# Femtoduino.net
KiCad netlist of a schematic drawn in EAGLE
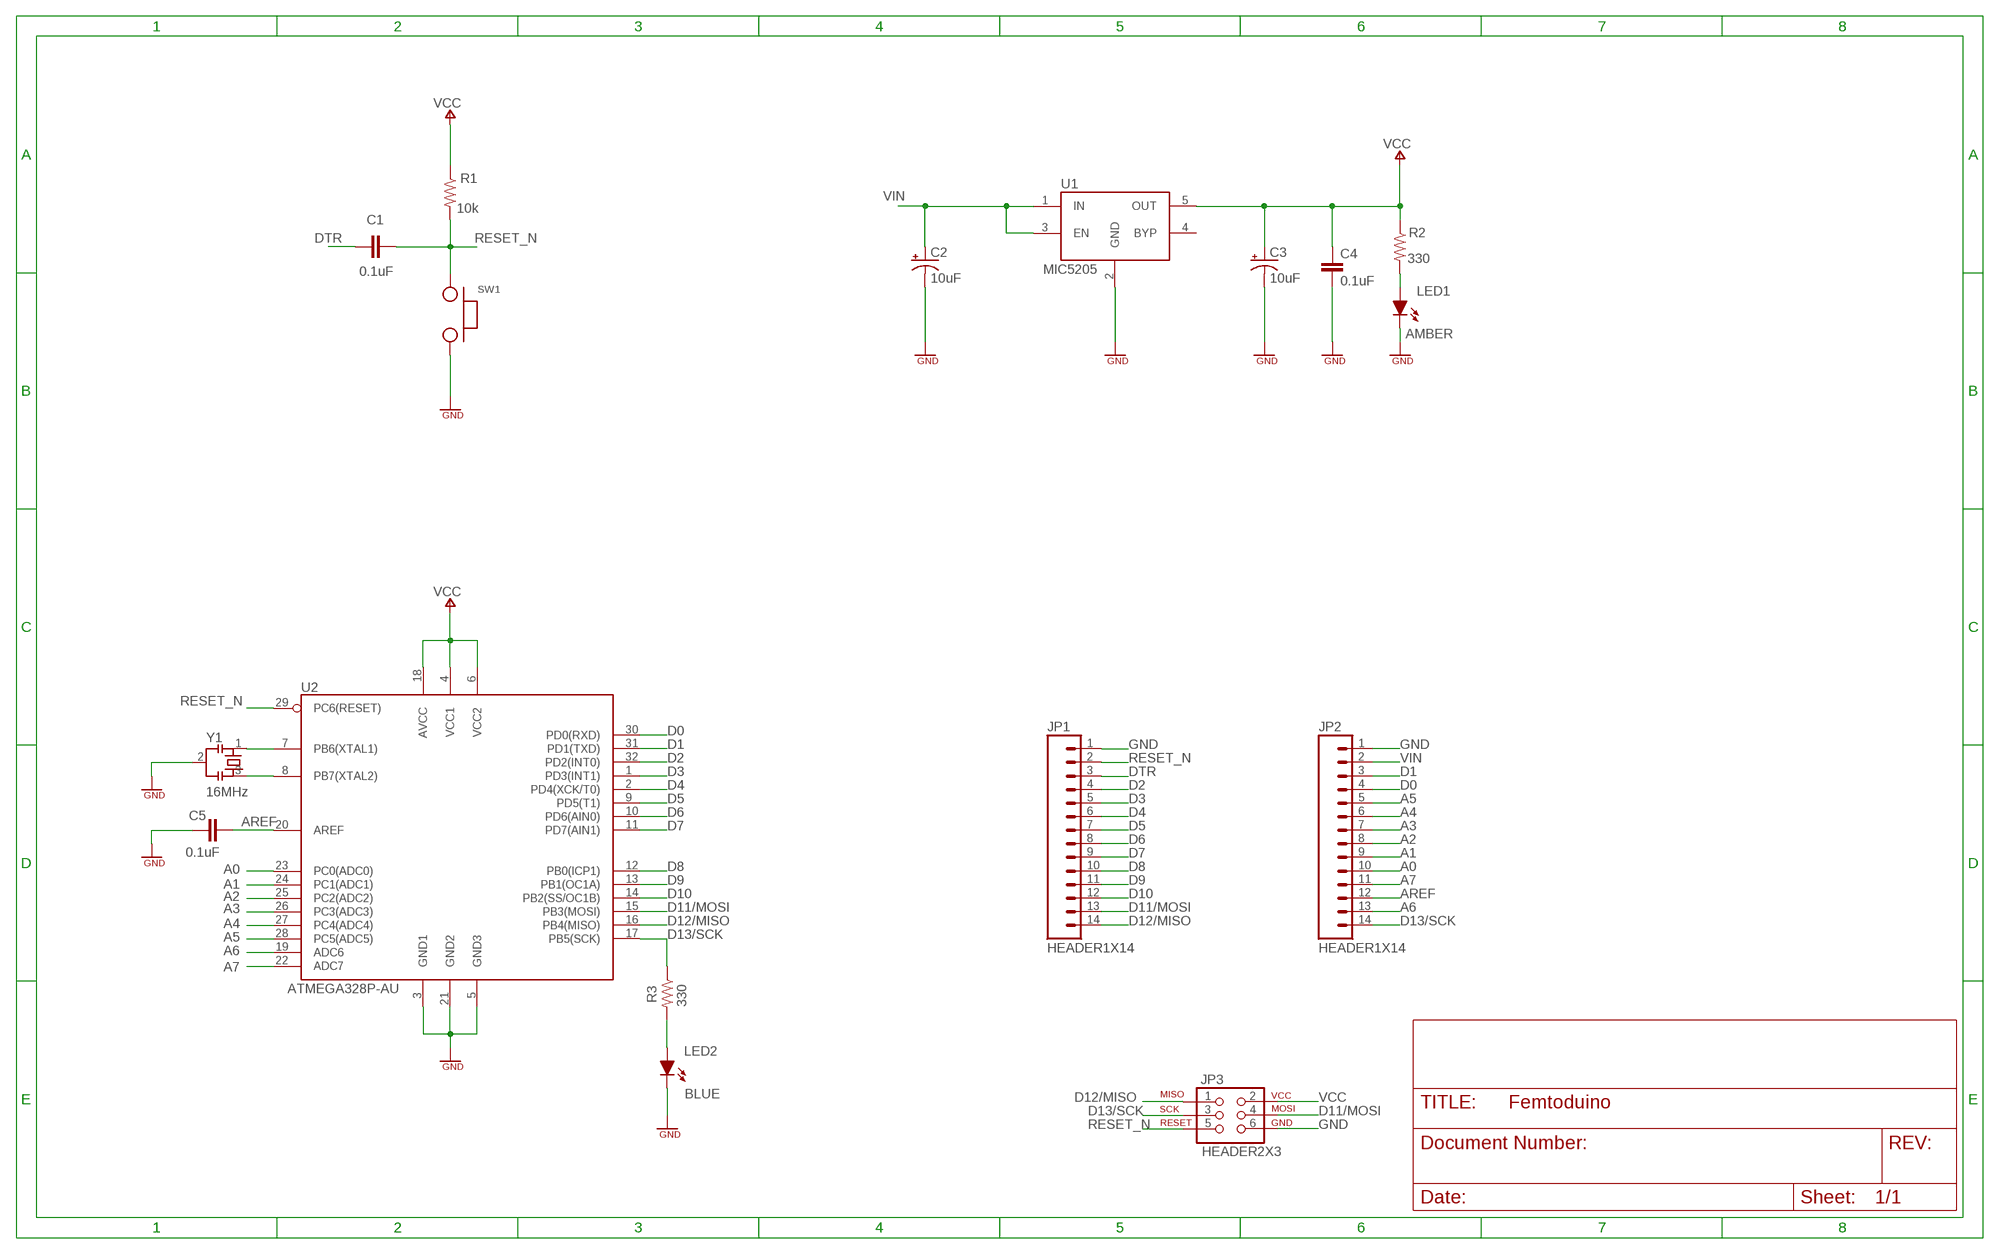
[diagram p0: schematic, sheet 1]

(export (version "E")
  (design (tool "Eeschema 10.0.6"))
  (components
    (comp (ref "C1")
      (value "0.1uF")
      (footprint "eagle-import:SMD0603")
      (libsource (lib "eagle-import") (part "CAP_0603"))
    )
    (comp (ref "C2")
      (value "10uF")
      (footprint "eagle-import:EIA3216")
      (libsource (lib "eagle-import") (part "CAP_TANT"))
    )
    (comp (ref "C3")
      (value "10uF")
      (footprint "eagle-import:EIA3216")
      (libsource (lib "eagle-import") (part "CAP_TANT"))
    )
    (comp (ref "C4")
      (value "0.1uF")
      (footprint "eagle-import:SMD0603")
      (libsource (lib "eagle-import") (part "CAP_0603"))
    )
    (comp (ref "C5")
      (value "0.1uF")
      (footprint "eagle-import:SMD0603")
      (libsource (lib "eagle-import") (part "CAP_0603"))
    )
    (comp (ref "JP1")
      (value "HEADER1X14")
      (footprint "eagle-import:1X14")
      (libsource (lib "eagle-import") (part "HEADER1X14"))
    )
    (comp (ref "JP2")
      (value "HEADER1X14")
      (footprint "eagle-import:1X14")
      (libsource (lib "eagle-import") (part "HEADER1X14"))
    )
    (comp (ref "JP3")
      (value "HEADER2X3")
      (footprint "eagle-import:2X3")
      (libsource (lib "eagle-import") (part "HEADER2X3"))
    )
    (comp (ref "LED1")
      (value "AMBER")
      (footprint "eagle-import:LED_0805")
      (libsource (lib "eagle-import") (part "LED_0805"))
    )
    (comp (ref "LED2")
      (value "BLUE")
      (footprint "eagle-import:LED_0805")
      (libsource (lib "eagle-import") (part "LED_0805"))
    )
    (comp (ref "R1")
      (value "10k")
      (footprint "eagle-import:SMD0603")
      (libsource (lib "eagle-import") (part "RES_0603"))
    )
    (comp (ref "R2")
      (value "330")
      (footprint "eagle-import:SMD0603")
      (libsource (lib "eagle-import") (part "RES_0603"))
    )
    (comp (ref "R3")
      (value "330")
      (footprint "eagle-import:SMD0603")
      (libsource (lib "eagle-import") (part "RES_0603"))
    )
    (comp (ref "SW1")
      (value "SWITCH")
      (footprint "eagle-import:SWITCH-SPST")
      (libsource (lib "eagle-import") (part "SWITCH"))
    )
    (comp (ref "U1")
      (value "MIC5205")
      (footprint "eagle-import:SOT23-5")
      (libsource (lib "eagle-import") (part "MIC5205"))
    )
    (comp (ref "U2")
      (value "ATMEGA328P-AU")
      (footprint "eagle-import:TQFP32")
      (libsource (lib "eagle-import") (part "ATMEGA328P-AU"))
    )
    (comp (ref "Y1")
      (value "16MHz")
      (footprint "eagle-import:CSTCE")
      (libsource (lib "eagle-import") (part "CSTCE"))
    )
  )
  (nets
    (net (code "1") (name "/A0") (class "Default")
      (node (ref "JP2") (pin "10") (pinfunction "10_10") (pintype "passive"))
      (node (ref "U2") (pin "23") (pinfunction "PC0(ADC0)_23") (pintype "bidirectional"))
    )
    (net (code "2") (name "/A1") (class "Default")
      (node (ref "JP2") (pin "9") (pinfunction "9_9") (pintype "passive"))
      (node (ref "U2") (pin "24") (pinfunction "PC1(ADC1)_24") (pintype "bidirectional"))
    )
    (net (code "3") (name "/A2") (class "Default")
      (node (ref "JP2") (pin "8") (pinfunction "8_8") (pintype "passive"))
      (node (ref "U2") (pin "25") (pinfunction "PC2(ADC2)_25") (pintype "bidirectional"))
    )
    (net (code "4") (name "/A3") (class "Default")
      (node (ref "JP2") (pin "7") (pinfunction "7_7") (pintype "passive"))
      (node (ref "U2") (pin "26") (pinfunction "PC3(ADC3)_26") (pintype "bidirectional"))
    )
    (net (code "5") (name "/A4") (class "Default")
      (node (ref "JP2") (pin "6") (pinfunction "6_6") (pintype "passive"))
      (node (ref "U2") (pin "27") (pinfunction "PC4(ADC4)_27") (pintype "bidirectional"))
    )
    (net (code "6") (name "/A5") (class "Default")
      (node (ref "JP2") (pin "5") (pinfunction "5_5") (pintype "passive"))
      (node (ref "U2") (pin "28") (pinfunction "PC5(ADC5)_28") (pintype "bidirectional"))
    )
    (net (code "7") (name "/A6") (class "Default")
      (node (ref "JP2") (pin "13") (pinfunction "13_13") (pintype "passive"))
      (node (ref "U2") (pin "19") (pinfunction "ADC6_19") (pintype "bidirectional"))
    )
    (net (code "8") (name "/A7") (class "Default")
      (node (ref "JP2") (pin "11") (pinfunction "11_11") (pintype "passive"))
      (node (ref "U2") (pin "22") (pinfunction "ADC7_22") (pintype "bidirectional"))
    )
    (net (code "9") (name "/AREF") (class "Default")
      (node (ref "C5") (pin "2") (pinfunction "2_2") (pintype "passive"))
      (node (ref "JP2") (pin "12") (pinfunction "12_12") (pintype "passive"))
      (node (ref "U2") (pin "20") (pinfunction "AREF_20") (pintype "bidirectional"))
    )
    (net (code "10") (name "/D0") (class "Default")
      (node (ref "JP2") (pin "4") (pinfunction "4_4") (pintype "passive"))
      (node (ref "U2") (pin "30") (pinfunction "PD0(RXD)_30") (pintype "bidirectional"))
    )
    (net (code "11") (name "/D1") (class "Default")
      (node (ref "JP2") (pin "3") (pinfunction "3_3") (pintype "passive"))
      (node (ref "U2") (pin "31") (pinfunction "PD1(TXD)_31") (pintype "bidirectional"))
    )
    (net (code "12") (name "/D2") (class "Default")
      (node (ref "JP1") (pin "4") (pinfunction "4_4") (pintype "passive"))
      (node (ref "U2") (pin "32") (pinfunction "PD2(INT0)_32") (pintype "bidirectional"))
    )
    (net (code "13") (name "/D3") (class "Default")
      (node (ref "JP1") (pin "5") (pinfunction "5_5") (pintype "passive"))
      (node (ref "U2") (pin "1") (pinfunction "PD3(INT1)_1") (pintype "bidirectional"))
    )
    (net (code "14") (name "/D4") (class "Default")
      (node (ref "JP1") (pin "6") (pinfunction "6_6") (pintype "passive"))
      (node (ref "U2") (pin "2") (pinfunction "PD4(XCK/T0)_2") (pintype "bidirectional"))
    )
    (net (code "15") (name "/D5") (class "Default")
      (node (ref "JP1") (pin "7") (pinfunction "7_7") (pintype "passive"))
      (node (ref "U2") (pin "9") (pinfunction "PD5(T1)_9") (pintype "bidirectional"))
    )
    (net (code "16") (name "/D6") (class "Default")
      (node (ref "JP1") (pin "8") (pinfunction "8_8") (pintype "passive"))
      (node (ref "U2") (pin "10") (pinfunction "PD6(AIN0)_10") (pintype "bidirectional"))
    )
    (net (code "17") (name "/D7") (class "Default")
      (node (ref "JP1") (pin "9") (pinfunction "9_9") (pintype "passive"))
      (node (ref "U2") (pin "11") (pinfunction "PD7(AIN1)_11") (pintype "bidirectional"))
    )
    (net (code "18") (name "/D8") (class "Default")
      (node (ref "JP1") (pin "10") (pinfunction "10_10") (pintype "passive"))
      (node (ref "U2") (pin "12") (pinfunction "PB0(ICP1)_12") (pintype "bidirectional"))
    )
    (net (code "19") (name "/D9") (class "Default")
      (node (ref "JP1") (pin "11") (pinfunction "11_11") (pintype "passive"))
      (node (ref "U2") (pin "13") (pinfunction "PB1(OC1A)_13") (pintype "bidirectional"))
    )
    (net (code "20") (name "/D10") (class "Default")
      (node (ref "JP1") (pin "12") (pinfunction "12_12") (pintype "passive"))
      (node (ref "U2") (pin "14") (pinfunction "PB2(SS/OC1B)_14") (pintype "bidirectional"))
    )
    (net (code "21") (name "/D11{slash}MOSI") (class "Default")
      (node (ref "JP1") (pin "13") (pinfunction "13_13") (pintype "passive"))
      (node (ref "JP3") (pin "4") (pinfunction "4_4") (pintype "passive"))
      (node (ref "U2") (pin "15") (pinfunction "PB3(MOSI)_15") (pintype "bidirectional"))
    )
    (net (code "22") (name "/D12{slash}MISO") (class "Default")
      (node (ref "JP1") (pin "14") (pinfunction "14_14") (pintype "passive"))
      (node (ref "JP3") (pin "1") (pinfunction "1_1") (pintype "passive"))
      (node (ref "U2") (pin "16") (pinfunction "PB4(MISO)_16") (pintype "bidirectional"))
    )
    (net (code "23") (name "/D13{slash}SCK") (class "Default")
      (node (ref "JP2") (pin "14") (pinfunction "14_14") (pintype "passive"))
      (node (ref "JP3") (pin "3") (pinfunction "3_3") (pintype "passive"))
      (node (ref "R3") (pin "1") (pinfunction "1_1") (pintype "passive"))
      (node (ref "U2") (pin "17") (pinfunction "PB5(SCK)_17") (pintype "bidirectional"))
    )
    (net (code "24") (name "/DTR") (class "Default")
      (node (ref "C1") (pin "1") (pinfunction "1_1") (pintype "passive"))
      (node (ref "JP1") (pin "3") (pinfunction "3_3") (pintype "passive"))
    )
    (net (code "25") (name "/RESET_N") (class "Default")
      (node (ref "C1") (pin "2") (pinfunction "2_2") (pintype "passive"))
      (node (ref "JP1") (pin "2") (pinfunction "2_2") (pintype "passive"))
      (node (ref "JP3") (pin "5") (pinfunction "5_5") (pintype "passive"))
      (node (ref "R1") (pin "2") (pinfunction "2_2") (pintype "passive"))
      (node (ref "SW1") (pin "1") (pinfunction "1_1") (pintype "bidirectional"))
      (node (ref "U2") (pin "29") (pinfunction "PC6(RESET)_29") (pintype "bidirectional"))
    )
    (net (code "26") (name "/VIN") (class "Default")
      (node (ref "C2") (pin "A") (pinfunction "+_A") (pintype "passive"))
      (node (ref "JP2") (pin "2") (pinfunction "2_2") (pintype "passive"))
      (node (ref "U1") (pin "1") (pinfunction "IN_1") (pintype "bidirectional"))
      (node (ref "U1") (pin "3") (pinfunction "EN_3") (pintype "bidirectional"))
    )
    (net (code "27") (name "GND") (class "Default")
      (node (ref "C2") (pin "C") (pinfunction "-_C") (pintype "passive"))
      (node (ref "C3") (pin "C") (pinfunction "-_C") (pintype "passive"))
      (node (ref "C4") (pin "2") (pinfunction "2_2") (pintype "passive"))
      (node (ref "C5") (pin "1") (pinfunction "1_1") (pintype "passive"))
      (node (ref "JP1") (pin "1") (pinfunction "1_1") (pintype "passive"))
      (node (ref "JP2") (pin "1") (pinfunction "1_1") (pintype "passive"))
      (node (ref "JP3") (pin "6") (pinfunction "6_6") (pintype "passive"))
      (node (ref "LED1") (pin "C") (pinfunction "C_C") (pintype "passive"))
      (node (ref "LED2") (pin "C") (pinfunction "C_C") (pintype "passive"))
      (node (ref "SW1") (pin "2") (pinfunction "2_2") (pintype "bidirectional"))
      (node (ref "U1") (pin "2") (pinfunction "GND_2") (pintype "bidirectional"))
      (node (ref "U2") (pin "21") (pinfunction "GND2_21") (pintype "bidirectional"))
      (node (ref "U2") (pin "3") (pinfunction "GND1_3") (pintype "bidirectional"))
      (node (ref "U2") (pin "5") (pinfunction "GND3_5") (pintype "bidirectional"))
      (node (ref "Y1") (pin "2") (pinfunction "2_2") (pintype "passive"))
    )
    (net (code "28") (name "Net-(LED1-PadA)") (class "Default")
      (node (ref "LED1") (pin "A") (pinfunction "A_A") (pintype "passive"))
      (node (ref "R2") (pin "2") (pinfunction "2_2") (pintype "passive"))
    )
    (net (code "29") (name "Net-(LED2-PadA)") (class "Default")
      (node (ref "LED2") (pin "A") (pinfunction "A_A") (pintype "passive"))
      (node (ref "R3") (pin "2") (pinfunction "2_2") (pintype "passive"))
    )
    (net (code "30") (name "Net-(U2-PB6(XTAL1))") (class "Default")
      (node (ref "U2") (pin "7") (pinfunction "PB6(XTAL1)_7") (pintype "bidirectional"))
      (node (ref "Y1") (pin "1") (pinfunction "1_1") (pintype "passive"))
    )
    (net (code "31") (name "Net-(U2-PB7(XTAL2))") (class "Default")
      (node (ref "U2") (pin "8") (pinfunction "PB7(XTAL2)_8") (pintype "bidirectional"))
      (node (ref "Y1") (pin "3") (pinfunction "3_3") (pintype "passive"))
    )
    (net (code "32") (name "VCC") (class "Default")
      (node (ref "C3") (pin "A") (pinfunction "+_A") (pintype "passive"))
      (node (ref "C4") (pin "1") (pinfunction "1_1") (pintype "passive"))
      (node (ref "JP3") (pin "2") (pinfunction "2_2") (pintype "passive"))
      (node (ref "R1") (pin "1") (pinfunction "1_1") (pintype "passive"))
      (node (ref "R2") (pin "1") (pinfunction "1_1") (pintype "passive"))
      (node (ref "U1") (pin "5") (pinfunction "OUT_5") (pintype "bidirectional"))
      (node (ref "U2") (pin "18") (pinfunction "AVCC_18") (pintype "bidirectional"))
      (node (ref "U2") (pin "4") (pinfunction "VCC1_4") (pintype "bidirectional"))
      (node (ref "U2") (pin "6") (pinfunction "VCC2_6") (pintype "bidirectional"))
    )
    (net (code "33") (name "unconnected-(U1-BYP-Pad4)") (class "Default")
      (node (ref "U1") (pin "4") (pinfunction "BYP_4") (pintype "passive"))
    )
  )
)
